# CATS-Vega-Pyro.net
KiCad netlist of a schematic drawn in Altium Designer
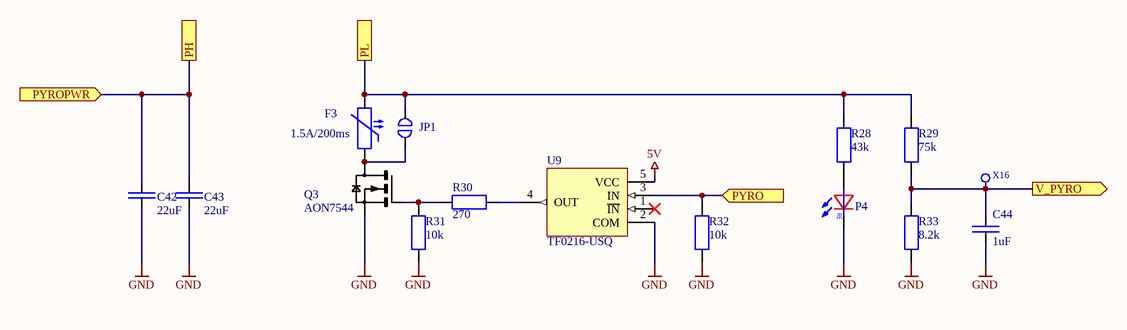
[diagram p0: CATS-Vega-Pyro.SchDoc]

(export (version "E")
  (design (tool "Eeschema 10.0.6"))
  (components
    (comp (ref "C42")
      (value "22uF")
      (footprint "SMD Keramikkondensator 0805")
      (description "SMD Ceramic Capacitor E6")
      (libsource (lib "CATS-EUROC") (part "E6 - 22uF"))
    )
    (comp (ref "C43")
      (value "22uF")
      (footprint "SMD Keramikkondensator 0805")
      (description "SMD Ceramic Capacitor E6")
      (libsource (lib "CATS-EUROC") (part "E6 - 22uF"))
    )
    (comp (ref "C44")
      (value "1uF")
      (footprint "SMD Keramikkondensator 0603")
      (description "SMD Ceramic Capacitor E6")
      (libsource (lib "CATS-EUROC") (part "E6 - 1uF"))
    )
    (comp (ref "F3")
      (value "1.5A/200ms")
      (footprint "SMD PPTC-Fuse 1206")
      (description "Polymeric PTC Resettable Fuse 30V 0.75A Surface Mount 1206")
      (libsource (lib "Other") (part "ASMD1206-075-30V"))
    )
    (comp (ref "JP1")
      (value "Jumper")
      (footprint "SMD Solder Jumper 1x2mm")
      (description "Single Position Jumper")
      (libsource (lib "Connectors") (part "Jumper-1"))
    )
    (comp (ref "P4")
      (value "LED")
      (footprint "SMD LED 0603")
      (description "Color LED")
      (libsource (lib "Diodes") (part "LED"))
    )
    (comp (ref "Q3")
      (value "AON7544")
      (footprint "SMD MOSFET DFN 3x3 EP")
      (description "N-Channel 30V 30A Surface Mount 8-DFN (3x3)")
      (libsource (lib "Electronic Switches") (part "AON7544"))
    )
    (comp (ref "R28")
      (value "43k")
      (footprint "SMD Widerstand 0603")
      (description "SMD Chip Resistor E24")
      (libsource (lib "Resistors-E24") (part "E24 - 43k"))
    )
    (comp (ref "R29")
      (value "75k")
      (footprint "SMD Widerstand 0603")
      (description "SMD Chip Resistor E24")
      (libsource (lib "Resistors-E24") (part "E24 - 75k"))
    )
    (comp (ref "R30")
      (value "270")
      (footprint "SMD Widerstand 0603")
      (description "SMD Chip Resistor E24")
      (libsource (lib "CATS-EUROC") (part "E24 - 270"))
    )
    (comp (ref "R31")
      (value "10k")
      (footprint "SMD Widerstand 0603")
      (description "SMD Chip Resistor E24")
      (libsource (lib "CATS-EUROC") (part "E24 - 10k"))
    )
    (comp (ref "R32")
      (value "10k")
      (footprint "SMD Widerstand 0603")
      (description "SMD Chip Resistor E24")
      (libsource (lib "CATS-EUROC") (part "E24 - 10k"))
    )
    (comp (ref "R33")
      (value "8.2k")
      (footprint "SMD Widerstand 0603")
      (description "SMD Chip Resistor E24")
      (libsource (lib "Resistors-E24") (part "E24 - 8.2k"))
    )
    (comp (ref "U9")
      (value "TF0216-USQ")
      (footprint "SMD IC SOT-23-5")
      (description "SOT-23-5L Gate Drive IC")
      (libsource (lib "Electronic Switches") (part "TF0216-USQ"))
    )
    (comp (ref "X16")
      (value "-")
      (footprint "SMD Test point 0.8mm")
      (description "Test Point SMD")
      (libsource (lib "Connectors") (part "SMD Test point"))
    )
  )
  (nets
    (net (code "1") (name "/PH") (class "Default")
      (node (ref "C42") (pin "2") (pinfunction "2_2") (pintype "passive"))
      (node (ref "C43") (pin "2") (pinfunction "2_2") (pintype "passive"))
    )
    (net (code "2") (name "/PL") (class "Default")
      (node (ref "F3") (pin "1") (pinfunction "1_1") (pintype "passive"))
      (node (ref "JP1") (pin "1") (pintype "passive"))
      (node (ref "R28") (pin "2") (pinfunction "2_2") (pintype "passive"))
      (node (ref "R29") (pin "2") (pinfunction "2_2") (pintype "passive"))
    )
    (net (code "3") (name "/PYRO") (class "Default")
      (node (ref "R32") (pin "2") (pinfunction "2_2") (pintype "passive"))
      (node (ref "U9") (pin "3") (pinfunction "IN_3") (pintype "input"))
    )
    (net (code "4") (name "/V_PYRO") (class "Default")
      (node (ref "C44") (pin "2") (pinfunction "2_2") (pintype "passive"))
      (node (ref "R29") (pin "1") (pinfunction "1_1") (pintype "passive"))
      (node (ref "R33") (pin "2") (pinfunction "2_2") (pintype "passive"))
      (node (ref "X16") (pin "1") (pinfunction "1_1") (pintype "passive"))
    )
    (net (code "5") (name "5V") (class "Default")
      (node (ref "U9") (pin "5") (pinfunction "VCC_5") (pintype "passive"))
    )
    (net (code "6") (name "GND") (class "Default")
      (node (ref "C42") (pin "1") (pinfunction "1_1") (pintype "passive"))
      (node (ref "C43") (pin "1") (pinfunction "1_1") (pintype "passive"))
      (node (ref "C44") (pin "1") (pinfunction "1_1") (pintype "passive"))
      (node (ref "P4") (pin "K") (pinfunction "K_K") (pintype "passive"))
      (node (ref "Q3") (pin "S") (pinfunction "S_S") (pintype "passive"))
      (node (ref "R31") (pin "1") (pinfunction "1_1") (pintype "passive"))
      (node (ref "R32") (pin "1") (pinfunction "1_1") (pintype "passive"))
      (node (ref "R33") (pin "1") (pinfunction "1_1") (pintype "passive"))
      (node (ref "U9") (pin "2") (pinfunction "COM_2") (pintype "passive"))
    )
    (net (code "7") (name "Net-(F3-Pad2)") (class "Default")
      (node (ref "F3") (pin "2") (pinfunction "2_2") (pintype "passive"))
      (node (ref "JP1") (pin "2") (pintype "passive"))
      (node (ref "Q3") (pin "D") (pinfunction "D_D") (pintype "passive"))
    )
    (net (code "8") (name "Net-(P4-PadA)") (class "Default")
      (node (ref "P4") (pin "A") (pinfunction "A_A") (pintype "passive"))
      (node (ref "R28") (pin "1") (pinfunction "1_1") (pintype "passive"))
    )
    (net (code "9") (name "Net-(Q3-PadG)") (class "Default")
      (node (ref "Q3") (pin "G") (pinfunction "G_G") (pintype "passive"))
      (node (ref "R30") (pin "1") (pinfunction "1_1") (pintype "passive"))
      (node (ref "R31") (pin "2") (pinfunction "2_2") (pintype "passive"))
    )
    (net (code "10") (name "Net-(U9-OUT)") (class "Default")
      (node (ref "R30") (pin "2") (pinfunction "2_2") (pintype "passive"))
      (node (ref "U9") (pin "4") (pinfunction "OUT_4") (pintype "output"))
    )
    (net (code "11") (name "unconnected-(U9-~{IN}-Pad1)") (class "Default")
      (node (ref "U9") (pin "1") (pinfunction "~{IN}_1") (pintype "input+no_connect"))
    )
  )
)
